# angle.net
KiCad netlist of a schematic drawn in EAGLE
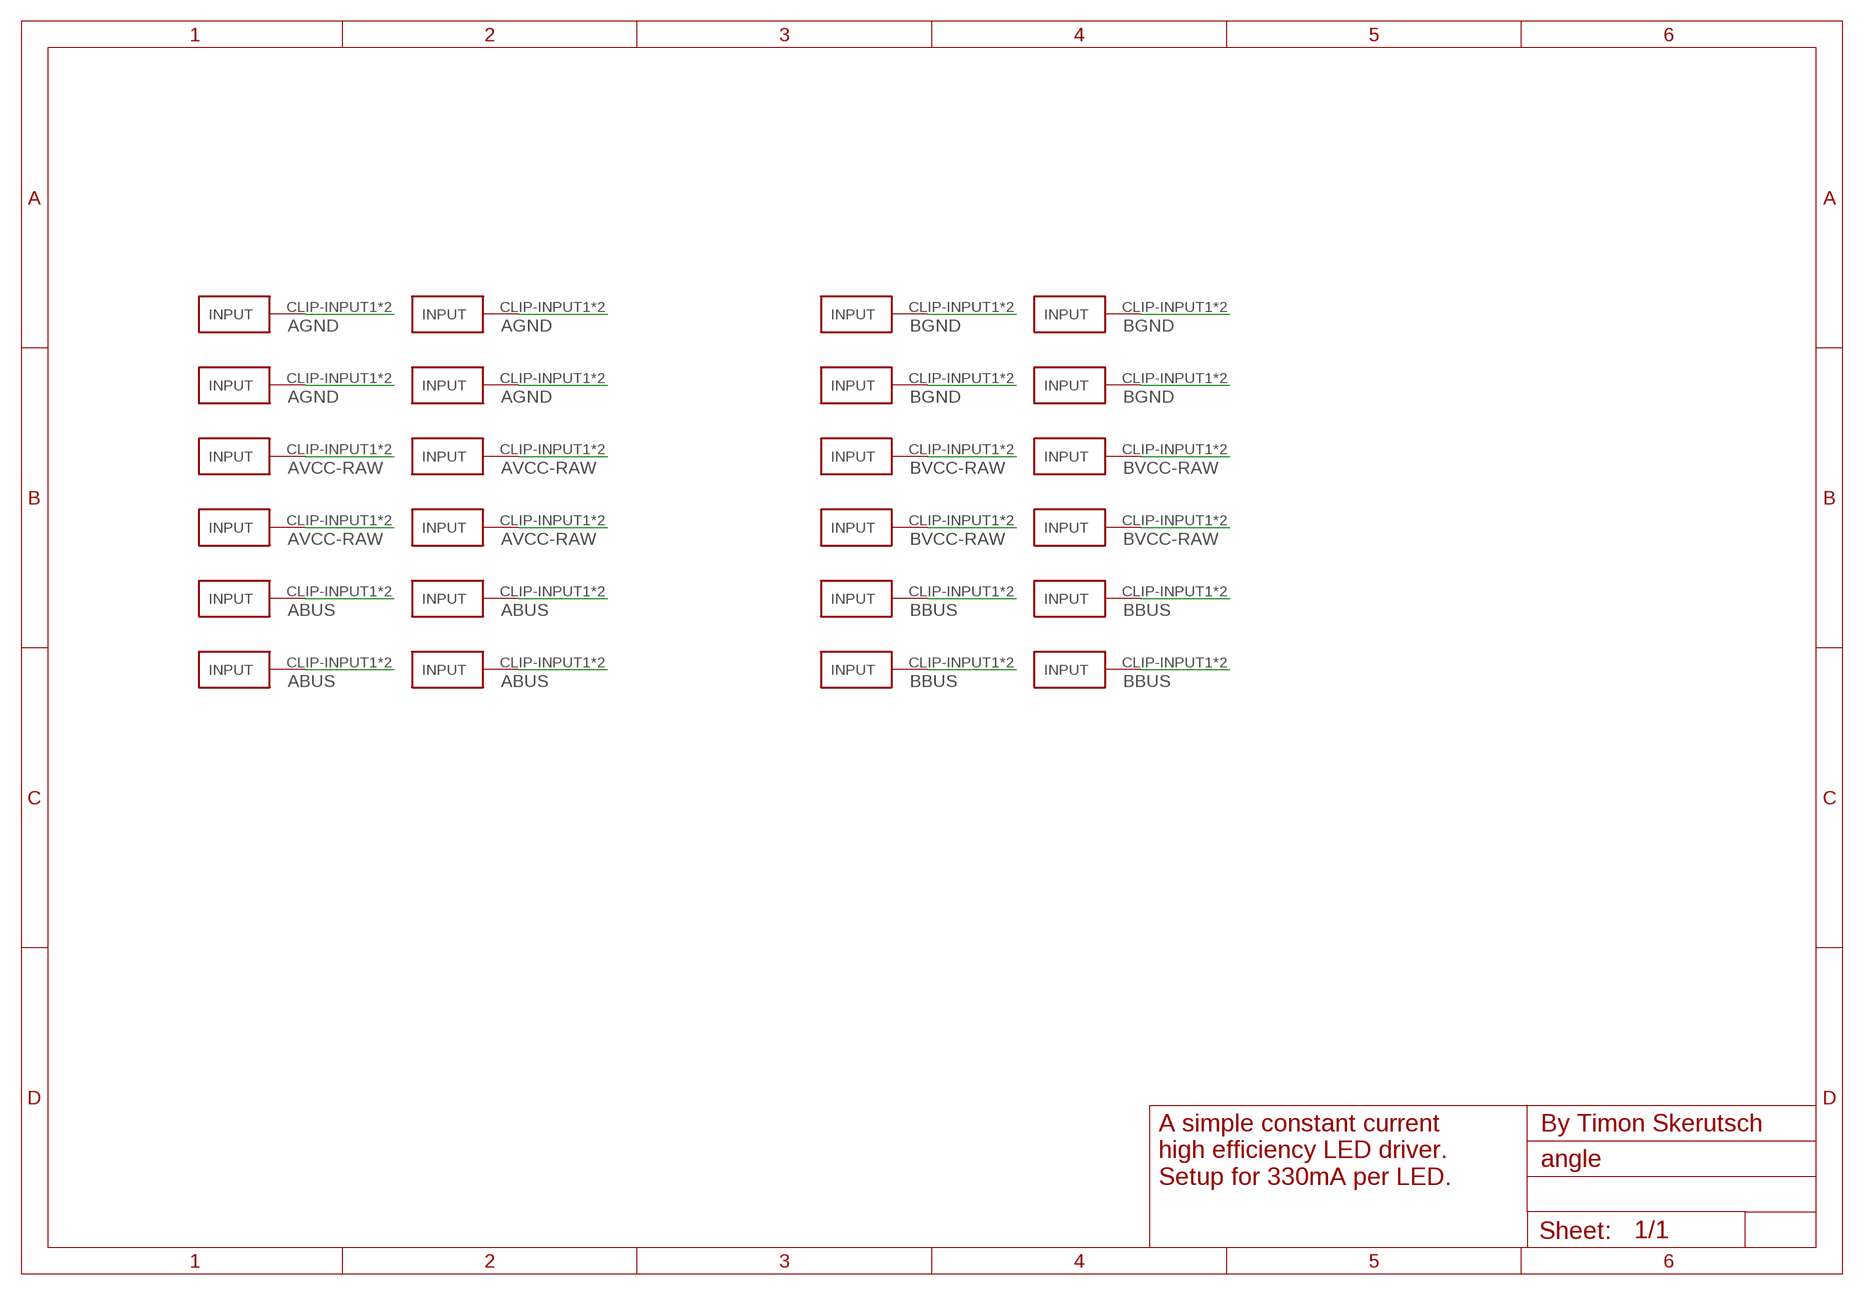
[diagram p0: schematic, sheet 1]

(export (version "E")
  (design (tool "Eeschema 10.0.6"))
  (components
    (comp (ref "ABUS-CLIP")
      (value "FUSE-HOLDER-5X20MM")
      (footprint "eagle-import:FUSE-HOLDER-5X20MM")
      (libsource (lib "eagle-import") (part "FUSE-HOLDER-5X20MM"))
    )
    (comp (ref "ABUS-CLIP1")
      (value "FUSE-HOLDER-5X20MM")
      (footprint "eagle-import:FUSE-HOLDER-5X20MM")
      (libsource (lib "eagle-import") (part "FUSE-HOLDER-5X20MM"))
    )
    (comp (ref "ABUS-CLIP2")
      (value "FUSE-HOLDER-5X20MM")
      (footprint "eagle-import:FUSE-HOLDER-5X20MM")
      (libsource (lib "eagle-import") (part "FUSE-HOLDER-5X20MM"))
    )
    (comp (ref "ABUS-CLIP3")
      (value "FUSE-HOLDER-5X20MM")
      (footprint "eagle-import:FUSE-HOLDER-5X20MM")
      (libsource (lib "eagle-import") (part "FUSE-HOLDER-5X20MM"))
    )
    (comp (ref "AGND-CLIP")
      (value "FUSE-HOLDER-5X20MM")
      (footprint "eagle-import:FUSE-HOLDER-5X20MM")
      (libsource (lib "eagle-import") (part "FUSE-HOLDER-5X20MM"))
    )
    (comp (ref "AGND-CLIP1")
      (value "FUSE-HOLDER-5X20MM")
      (footprint "eagle-import:FUSE-HOLDER-5X20MM")
      (libsource (lib "eagle-import") (part "FUSE-HOLDER-5X20MM"))
    )
    (comp (ref "AGND-CLIP2")
      (value "FUSE-HOLDER-5X20MM")
      (footprint "eagle-import:FUSE-HOLDER-5X20MM")
      (libsource (lib "eagle-import") (part "FUSE-HOLDER-5X20MM"))
    )
    (comp (ref "AGND-CLIP3")
      (value "FUSE-HOLDER-5X20MM")
      (footprint "eagle-import:FUSE-HOLDER-5X20MM")
      (libsource (lib "eagle-import") (part "FUSE-HOLDER-5X20MM"))
    )
    (comp (ref "AVCC-CLIP")
      (value "FUSE-HOLDER-5X20MM")
      (footprint "eagle-import:FUSE-HOLDER-5X20MM")
      (libsource (lib "eagle-import") (part "FUSE-HOLDER-5X20MM"))
    )
    (comp (ref "AVCC-CLIP1")
      (value "FUSE-HOLDER-5X20MM")
      (footprint "eagle-import:FUSE-HOLDER-5X20MM")
      (libsource (lib "eagle-import") (part "FUSE-HOLDER-5X20MM"))
    )
    (comp (ref "AVCC-CLIP2")
      (value "FUSE-HOLDER-5X20MM")
      (footprint "eagle-import:FUSE-HOLDER-5X20MM")
      (libsource (lib "eagle-import") (part "FUSE-HOLDER-5X20MM"))
    )
    (comp (ref "AVCC-CLIP3")
      (value "FUSE-HOLDER-5X20MM")
      (footprint "eagle-import:FUSE-HOLDER-5X20MM")
      (libsource (lib "eagle-import") (part "FUSE-HOLDER-5X20MM"))
    )
    (comp (ref "BBUS-CLIP")
      (value "FUSE-HOLDER-5X20MM")
      (footprint "eagle-import:FUSE-HOLDER-5X20MM")
      (libsource (lib "eagle-import") (part "FUSE-HOLDER-5X20MM"))
    )
    (comp (ref "BBUS-CLIP1")
      (value "FUSE-HOLDER-5X20MM")
      (footprint "eagle-import:FUSE-HOLDER-5X20MM")
      (libsource (lib "eagle-import") (part "FUSE-HOLDER-5X20MM"))
    )
    (comp (ref "BBUS-CLIP2")
      (value "FUSE-HOLDER-5X20MM")
      (footprint "eagle-import:FUSE-HOLDER-5X20MM")
      (libsource (lib "eagle-import") (part "FUSE-HOLDER-5X20MM"))
    )
    (comp (ref "BBUS-CLIP3")
      (value "FUSE-HOLDER-5X20MM")
      (footprint "eagle-import:FUSE-HOLDER-5X20MM")
      (libsource (lib "eagle-import") (part "FUSE-HOLDER-5X20MM"))
    )
    (comp (ref "BGND-CLIP")
      (value "FUSE-HOLDER-5X20MM")
      (footprint "eagle-import:FUSE-HOLDER-5X20MM")
      (libsource (lib "eagle-import") (part "FUSE-HOLDER-5X20MM"))
    )
    (comp (ref "BGND-CLIP1")
      (value "FUSE-HOLDER-5X20MM")
      (footprint "eagle-import:FUSE-HOLDER-5X20MM")
      (libsource (lib "eagle-import") (part "FUSE-HOLDER-5X20MM"))
    )
    (comp (ref "BGND-CLIP2")
      (value "FUSE-HOLDER-5X20MM")
      (footprint "eagle-import:FUSE-HOLDER-5X20MM")
      (libsource (lib "eagle-import") (part "FUSE-HOLDER-5X20MM"))
    )
    (comp (ref "BGND-CLIP3")
      (value "FUSE-HOLDER-5X20MM")
      (footprint "eagle-import:FUSE-HOLDER-5X20MM")
      (libsource (lib "eagle-import") (part "FUSE-HOLDER-5X20MM"))
    )
    (comp (ref "BVCC-CLIP")
      (value "FUSE-HOLDER-5X20MM")
      (footprint "eagle-import:FUSE-HOLDER-5X20MM")
      (libsource (lib "eagle-import") (part "FUSE-HOLDER-5X20MM"))
    )
    (comp (ref "BVCC-CLIP1")
      (value "FUSE-HOLDER-5X20MM")
      (footprint "eagle-import:FUSE-HOLDER-5X20MM")
      (libsource (lib "eagle-import") (part "FUSE-HOLDER-5X20MM"))
    )
    (comp (ref "BVCC-CLIP2")
      (value "FUSE-HOLDER-5X20MM")
      (footprint "eagle-import:FUSE-HOLDER-5X20MM")
      (libsource (lib "eagle-import") (part "FUSE-HOLDER-5X20MM"))
    )
    (comp (ref "BVCC-CLIP3")
      (value "FUSE-HOLDER-5X20MM")
      (footprint "eagle-import:FUSE-HOLDER-5X20MM")
      (libsource (lib "eagle-import") (part "FUSE-HOLDER-5X20MM"))
    )
  )
  (nets
    (net (code "1") (name "/ABUS") (class "Default")
      (node (ref "ABUS-CLIP") (pin "CLIP-INPUT1") (pinfunction "INPUT_CLIP-INPUT1") (pintype "bidirectional"))
      (node (ref "ABUS-CLIP") (pin "CLIP-INPUT2") (pinfunction "INPUT_CLIP-INPUT2") (pintype "bidirectional"))
      (node (ref "ABUS-CLIP1") (pin "CLIP-INPUT1") (pinfunction "INPUT_CLIP-INPUT1") (pintype "bidirectional"))
      (node (ref "ABUS-CLIP1") (pin "CLIP-INPUT2") (pinfunction "INPUT_CLIP-INPUT2") (pintype "bidirectional"))
      (node (ref "ABUS-CLIP2") (pin "CLIP-INPUT1") (pinfunction "INPUT_CLIP-INPUT1") (pintype "bidirectional"))
      (node (ref "ABUS-CLIP2") (pin "CLIP-INPUT2") (pinfunction "INPUT_CLIP-INPUT2") (pintype "bidirectional"))
      (node (ref "ABUS-CLIP3") (pin "CLIP-INPUT1") (pinfunction "INPUT_CLIP-INPUT1") (pintype "bidirectional"))
      (node (ref "ABUS-CLIP3") (pin "CLIP-INPUT2") (pinfunction "INPUT_CLIP-INPUT2") (pintype "bidirectional"))
    )
    (net (code "2") (name "/AGND") (class "Default")
      (node (ref "AGND-CLIP") (pin "CLIP-INPUT1") (pinfunction "INPUT_CLIP-INPUT1") (pintype "bidirectional"))
      (node (ref "AGND-CLIP") (pin "CLIP-INPUT2") (pinfunction "INPUT_CLIP-INPUT2") (pintype "bidirectional"))
      (node (ref "AGND-CLIP1") (pin "CLIP-INPUT1") (pinfunction "INPUT_CLIP-INPUT1") (pintype "bidirectional"))
      (node (ref "AGND-CLIP1") (pin "CLIP-INPUT2") (pinfunction "INPUT_CLIP-INPUT2") (pintype "bidirectional"))
      (node (ref "AGND-CLIP2") (pin "CLIP-INPUT1") (pinfunction "INPUT_CLIP-INPUT1") (pintype "bidirectional"))
      (node (ref "AGND-CLIP2") (pin "CLIP-INPUT2") (pinfunction "INPUT_CLIP-INPUT2") (pintype "bidirectional"))
      (node (ref "AGND-CLIP3") (pin "CLIP-INPUT1") (pinfunction "INPUT_CLIP-INPUT1") (pintype "bidirectional"))
      (node (ref "AGND-CLIP3") (pin "CLIP-INPUT2") (pinfunction "INPUT_CLIP-INPUT2") (pintype "bidirectional"))
    )
    (net (code "3") (name "/AVCC-RAW") (class "Default")
      (node (ref "AVCC-CLIP") (pin "CLIP-INPUT1") (pinfunction "INPUT_CLIP-INPUT1") (pintype "bidirectional"))
      (node (ref "AVCC-CLIP") (pin "CLIP-INPUT2") (pinfunction "INPUT_CLIP-INPUT2") (pintype "bidirectional"))
      (node (ref "AVCC-CLIP1") (pin "CLIP-INPUT1") (pinfunction "INPUT_CLIP-INPUT1") (pintype "bidirectional"))
      (node (ref "AVCC-CLIP1") (pin "CLIP-INPUT2") (pinfunction "INPUT_CLIP-INPUT2") (pintype "bidirectional"))
      (node (ref "AVCC-CLIP2") (pin "CLIP-INPUT1") (pinfunction "INPUT_CLIP-INPUT1") (pintype "bidirectional"))
      (node (ref "AVCC-CLIP2") (pin "CLIP-INPUT2") (pinfunction "INPUT_CLIP-INPUT2") (pintype "bidirectional"))
      (node (ref "AVCC-CLIP3") (pin "CLIP-INPUT1") (pinfunction "INPUT_CLIP-INPUT1") (pintype "bidirectional"))
      (node (ref "AVCC-CLIP3") (pin "CLIP-INPUT2") (pinfunction "INPUT_CLIP-INPUT2") (pintype "bidirectional"))
    )
    (net (code "4") (name "/BBUS") (class "Default")
      (node (ref "BBUS-CLIP") (pin "CLIP-INPUT1") (pinfunction "INPUT_CLIP-INPUT1") (pintype "bidirectional"))
      (node (ref "BBUS-CLIP") (pin "CLIP-INPUT2") (pinfunction "INPUT_CLIP-INPUT2") (pintype "bidirectional"))
      (node (ref "BBUS-CLIP1") (pin "CLIP-INPUT1") (pinfunction "INPUT_CLIP-INPUT1") (pintype "bidirectional"))
      (node (ref "BBUS-CLIP1") (pin "CLIP-INPUT2") (pinfunction "INPUT_CLIP-INPUT2") (pintype "bidirectional"))
      (node (ref "BBUS-CLIP2") (pin "CLIP-INPUT1") (pinfunction "INPUT_CLIP-INPUT1") (pintype "bidirectional"))
      (node (ref "BBUS-CLIP2") (pin "CLIP-INPUT2") (pinfunction "INPUT_CLIP-INPUT2") (pintype "bidirectional"))
      (node (ref "BBUS-CLIP3") (pin "CLIP-INPUT1") (pinfunction "INPUT_CLIP-INPUT1") (pintype "bidirectional"))
      (node (ref "BBUS-CLIP3") (pin "CLIP-INPUT2") (pinfunction "INPUT_CLIP-INPUT2") (pintype "bidirectional"))
    )
    (net (code "5") (name "/BGND") (class "Default")
      (node (ref "BGND-CLIP") (pin "CLIP-INPUT1") (pinfunction "INPUT_CLIP-INPUT1") (pintype "bidirectional"))
      (node (ref "BGND-CLIP") (pin "CLIP-INPUT2") (pinfunction "INPUT_CLIP-INPUT2") (pintype "bidirectional"))
      (node (ref "BGND-CLIP1") (pin "CLIP-INPUT1") (pinfunction "INPUT_CLIP-INPUT1") (pintype "bidirectional"))
      (node (ref "BGND-CLIP1") (pin "CLIP-INPUT2") (pinfunction "INPUT_CLIP-INPUT2") (pintype "bidirectional"))
      (node (ref "BGND-CLIP2") (pin "CLIP-INPUT1") (pinfunction "INPUT_CLIP-INPUT1") (pintype "bidirectional"))
      (node (ref "BGND-CLIP2") (pin "CLIP-INPUT2") (pinfunction "INPUT_CLIP-INPUT2") (pintype "bidirectional"))
      (node (ref "BGND-CLIP3") (pin "CLIP-INPUT1") (pinfunction "INPUT_CLIP-INPUT1") (pintype "bidirectional"))
      (node (ref "BGND-CLIP3") (pin "CLIP-INPUT2") (pinfunction "INPUT_CLIP-INPUT2") (pintype "bidirectional"))
    )
    (net (code "6") (name "/BVCC-RAW") (class "Default")
      (node (ref "BVCC-CLIP") (pin "CLIP-INPUT1") (pinfunction "INPUT_CLIP-INPUT1") (pintype "bidirectional"))
      (node (ref "BVCC-CLIP") (pin "CLIP-INPUT2") (pinfunction "INPUT_CLIP-INPUT2") (pintype "bidirectional"))
      (node (ref "BVCC-CLIP1") (pin "CLIP-INPUT1") (pinfunction "INPUT_CLIP-INPUT1") (pintype "bidirectional"))
      (node (ref "BVCC-CLIP1") (pin "CLIP-INPUT2") (pinfunction "INPUT_CLIP-INPUT2") (pintype "bidirectional"))
      (node (ref "BVCC-CLIP2") (pin "CLIP-INPUT1") (pinfunction "INPUT_CLIP-INPUT1") (pintype "bidirectional"))
      (node (ref "BVCC-CLIP2") (pin "CLIP-INPUT2") (pinfunction "INPUT_CLIP-INPUT2") (pintype "bidirectional"))
      (node (ref "BVCC-CLIP3") (pin "CLIP-INPUT1") (pinfunction "INPUT_CLIP-INPUT1") (pintype "bidirectional"))
      (node (ref "BVCC-CLIP3") (pin "CLIP-INPUT2") (pinfunction "INPUT_CLIP-INPUT2") (pintype "bidirectional"))
    )
  )
)
